# motor_driver_1.net
KiCad netlist of a schematic drawn in Altium Designer
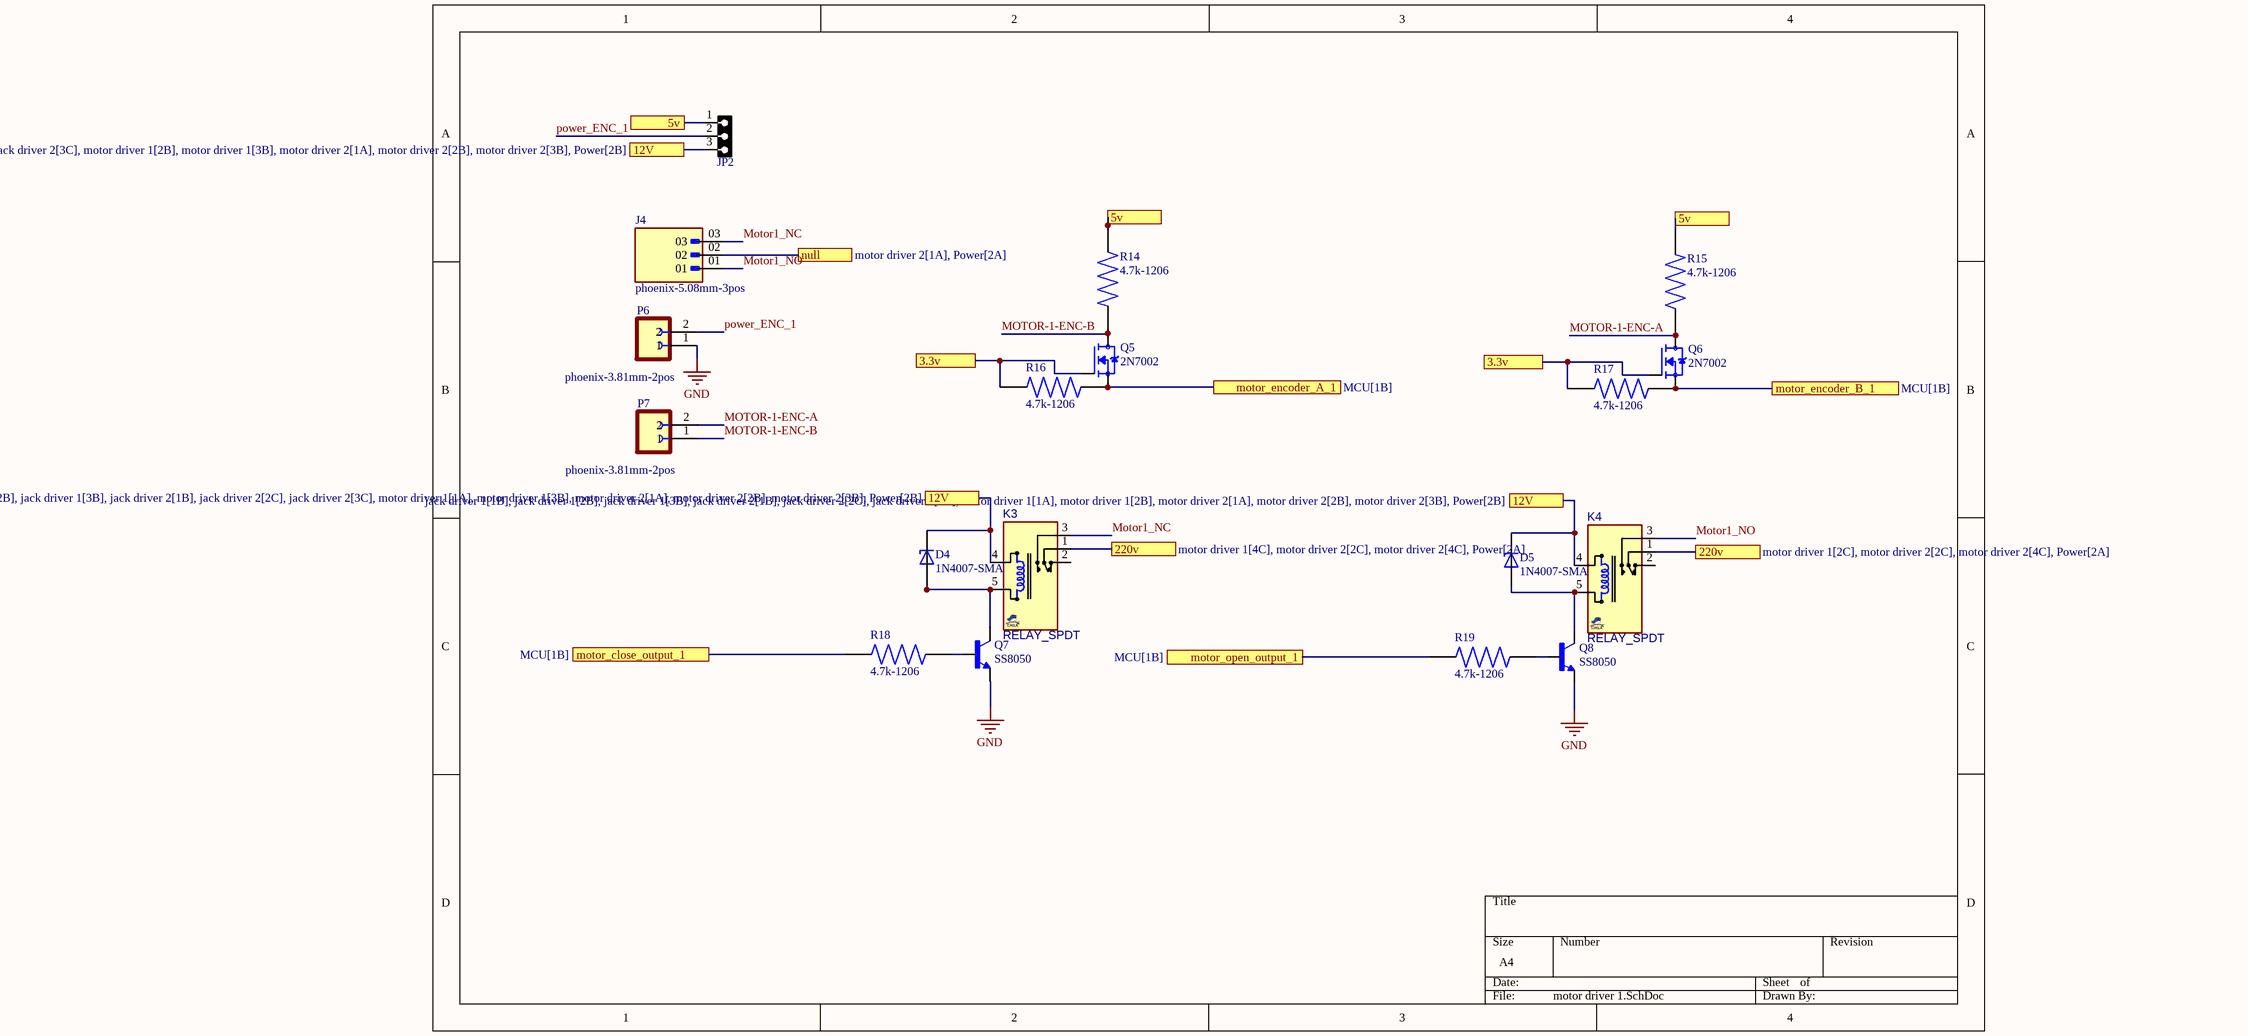
[diagram p0: motor driver 1.SchDoc]

(export (version "E")
  (design (tool "Eeschema 10.0.6"))
  (components
    (comp (ref "D4")
      (value "1N4007-SMA")
      (footprint "DIOM4325X250N")
      (description "400W, 30.4V, 5%, Unidirectional, TVS")
      (fields (field (name "MF") "Taiwan Semiconductor") (field (name "MP") "SMAJ26A"))
      (libsource (lib "diode-sma") (part "SMAJ26A"))
    )
    (comp (ref "D5")
      (value "1N4007-SMA")
      (footprint "DIOM4325X250N")
      (description "400W, 30.4V, 5%, Unidirectional, TVS")
      (fields (field (name "MF") "Taiwan Semiconductor") (field (name "MP") "SMAJ26A"))
      (libsource (lib "diode-sma") (part "SMAJ26A"))
    )
    (comp (ref "J4")
      (value "phoenix-5.08mm-3pos")
      (footprint "PHOENIX_1759020")
      (description "Pluggable Header 5.08mm 12AWG 320V 12A 3 Position COMBICON MSTB Series ¦ Phoenix Contact 1759020")
      (fields (field (name "MF") "Phoenix Contact") (field (name "MP") "1759020"))
      (libsource (lib "phoenix-3pos") (part "1759020"))
    )
    (comp (ref "JP2")
      (value "HDRF3")
      (footprint "HDRLP_F_1X3")
      (description "CONN, HEADER, Male, pitch: 2.54mm, 3POS")
      (libsource (lib "conn_2.54mm_lp") (part "HDRLP_F_1X3"))
    )
    (comp (ref "K3")
      (value "RELAY_SPDT")
      (footprint "REL_SPDT_5_1512")
      (description "Relay, SPDT, 5P, 15.4X12.1mm, 16V/30A")
      (fields (field (name "MANF") "OMRON") (field (name "MANF_P#") "G8QN-1C4 DC12"))
      (libsource (lib "relay") (part "RELAY_SPDT_5_1512_G8QN"))
    )
    (comp (ref "K4")
      (value "RELAY_SPDT")
      (footprint "REL_SPDT_5_1512")
      (description "Relay, SPDT, 5P, 15.4X12.1mm, 16V/30A")
      (fields (field (name "MANF") "OMRON") (field (name "MANF_P#") "G8QN-1C4 DC12"))
      (libsource (lib "relay") (part "RELAY_SPDT_5_1512_G8QN"))
    )
    (comp (ref "P6")
      (value "phoenix-3.81mm-2pos")
      (footprint "PHOENIX_1803578")
      (description "2 Position Terminal Block Plug, Female Sockets 0.150 (3.81mm) 180Â° Free Hanging (In-Line)")
      (fields (field (name "MF") "Phoenix Contact") (field (name "MP") "1803578"))
      (libsource (lib "terminal-phoenix-3.81mm-2pos") (part "1803578"))
    )
    (comp (ref "P7")
      (value "phoenix-3.81mm-2pos")
      (footprint "PHOENIX_1803578")
      (description "2 Position Terminal Block Plug, Female Sockets 0.150 (3.81mm) 180Â° Free Hanging (In-Line)")
      (fields (field (name "MF") "Phoenix Contact") (field (name "MP") "1803578"))
      (libsource (lib "terminal-phoenix-3.81mm-2pos") (part "1803578"))
    )
    (comp (ref "Q5")
      (value "2N7002")
      (footprint "SOT95P240X111-3N")
      (description "N-Channel 60V 280mA (Ta) 350mW (Ta) Surface Mount SOT-23-3 (TO-236)")
      (fields (field (name "MF") "{'manufacturer': u'onsemi'}"))
      (libsource (lib "2N7002-SOT23") (part "2N7002"))
    )
    (comp (ref "Q6")
      (value "2N7002")
      (footprint "SOT95P240X111-3N")
      (description "N-Channel 60V 280mA (Ta) 350mW (Ta) Surface Mount SOT-23-3 (TO-236)")
      (fields (field (name "MF") "{'manufacturer': u'onsemi'}"))
      (libsource (lib "2N7002-SOT23") (part "2N7002"))
    )
    (comp (ref "Q7")
      (value "SS8050")
      (footprint "TRANS_SS8050-G")
      (description "Bipolar (BJT) Transistor NPN 25 V 1.5 A 100MHz 300 mW Surface Mount SOT-23-3")
      (fields (field (name "DIGI-KEY_PART_NUMBER") "641-1790-2-ND") (field (name "MP") "SS8050G"))
      (libsource (lib "SS8050-G") (part "SS8050-G"))
    )
    (comp (ref "Q8")
      (value "SS8050")
      (footprint "TRANS_SS8050-G")
      (description "Bipolar (BJT) Transistor NPN 25 V 1.5 A 100MHz 300 mW Surface Mount SOT-23-3")
      (fields (field (name "DIGI-KEY_PART_NUMBER") "641-1790-2-ND") (field (name "MP") "SS8050G"))
      (libsource (lib "SS8050-G") (part "SS8050-G"))
    )
    (comp (ref "R14")
      (value "4.7k-1206")
      (footprint "RESC3015X65N")
      (description "Res Thin Film 1206 10K Ohm 0.1% 1/8W Â±25ppm/Â°C Molded SMD SMD Paper T/R")
      (fields (field (name "MF") "TE Connectivity") (field (name "MP") "CPF1206B10KE1"))
      (libsource (lib "resistor-1206") (part "CPF1206B10KE1"))
    )
    (comp (ref "R15")
      (value "4.7k-1206")
      (footprint "RESC3015X65N")
      (description "Res Thin Film 1206 10K Ohm 0.1% 1/8W Â±25ppm/Â°C Molded SMD SMD Paper T/R")
      (fields (field (name "MF") "TE Connectivity") (field (name "MP") "CPF1206B10KE1"))
      (libsource (lib "resistor-1206") (part "CPF1206B10KE1"))
    )
    (comp (ref "R16")
      (value "4.7k-1206")
      (footprint "RESC3015X65N")
      (description "Res Thin Film 1206 10K Ohm 0.1% 1/8W Â±25ppm/Â°C Molded SMD SMD Paper T/R")
      (fields (field (name "MF") "TE Connectivity") (field (name "MP") "CPF1206B10KE1"))
      (libsource (lib "resistor-1206") (part "CPF1206B10KE1"))
    )
    (comp (ref "R17")
      (value "4.7k-1206")
      (footprint "RESC3015X65N")
      (description "Res Thin Film 1206 10K Ohm 0.1% 1/8W Â±25ppm/Â°C Molded SMD SMD Paper T/R")
      (fields (field (name "MF") "TE Connectivity") (field (name "MP") "CPF1206B10KE1"))
      (libsource (lib "resistor-1206") (part "CPF1206B10KE1"))
    )
    (comp (ref "R18")
      (value "4.7k-1206")
      (footprint "RESC3015X65N")
      (description "Res Thin Film 1206 10K Ohm 0.1% 1/8W Â±25ppm/Â°C Molded SMD SMD Paper T/R")
      (fields (field (name "MF") "TE Connectivity") (field (name "MP") "CPF1206B10KE1"))
      (libsource (lib "resistor-1206") (part "CPF1206B10KE1"))
    )
    (comp (ref "R19")
      (value "4.7k-1206")
      (footprint "RESC3015X65N")
      (description "Res Thin Film 1206 10K Ohm 0.1% 1/8W Â±25ppm/Â°C Molded SMD SMD Paper T/R")
      (fields (field (name "MF") "TE Connectivity") (field (name "MP") "CPF1206B10KE1"))
      (libsource (lib "resistor-1206") (part "CPF1206B10KE1"))
    )
  )
  (nets
    (net (code "1") (name "/3.3v") (class "Default")
      (node (ref "Q5") (pin "1") (pinfunction "G_1") (pintype "passive"))
      (node (ref "Q6") (pin "1") (pinfunction "G_1") (pintype "passive"))
      (node (ref "R16") (pin "2") (pinfunction "2_2") (pintype "passive"))
      (node (ref "R17") (pin "2") (pinfunction "2_2") (pintype "passive"))
    )
    (net (code "2") (name "/5v") (class "Default")
      (node (ref "JP2") (pin "1") (pinfunction "1_1") (pintype "passive"))
      (node (ref "R14") (pin "2") (pinfunction "2_2") (pintype "passive"))
      (node (ref "R15") (pin "2") (pinfunction "2_2") (pintype "passive"))
    )
    (net (code "3") (name "/12V") (class "Default")
      (node (ref "D4") (pin "C") (pinfunction "C_C") (pintype "passive"))
      (node (ref "D5") (pin "C") (pinfunction "C_C") (pintype "passive"))
      (node (ref "JP2") (pin "3") (pinfunction "3_3") (pintype "passive"))
      (node (ref "K3") (pin "4") (pinfunction "T1_4") (pintype "passive"))
      (node (ref "K4") (pin "4") (pinfunction "T1_4") (pintype "passive"))
    )
    (net (code "4") (name "/220v") (class "Default")
      (node (ref "K3") (pin "1") (pinfunction "COM_1") (pintype "passive"))
      (node (ref "K4") (pin "1") (pinfunction "COM_1") (pintype "passive"))
    )
    (net (code "5") (name "/MOTOR-1-ENC-A") (class "Default")
      (node (ref "P7") (pin "2") (pinfunction "2_2") (pintype "passive"))
      (node (ref "Q6") (pin "3") (pinfunction "D_3") (pintype "passive"))
      (node (ref "R15") (pin "1") (pinfunction "1_1") (pintype "passive"))
    )
    (net (code "6") (name "/MOTOR-1-ENC-B") (class "Default")
      (node (ref "P7") (pin "1") (pinfunction "1_1") (pintype "passive"))
      (node (ref "Q5") (pin "3") (pinfunction "D_3") (pintype "passive"))
      (node (ref "R14") (pin "1") (pinfunction "1_1") (pintype "passive"))
    )
    (net (code "7") (name "/Motor1_NC") (class "Default")
      (node (ref "J4") (pin "03") (pinfunction "03_03") (pintype "passive"))
      (node (ref "K3") (pin "3") (pinfunction "NO_3") (pintype "passive"))
    )
    (net (code "8") (name "/Motor1_NO") (class "Default")
      (node (ref "J4") (pin "01") (pinfunction "01_01") (pintype "passive"))
      (node (ref "K4") (pin "3") (pinfunction "NO_3") (pintype "passive"))
    )
    (net (code "9") (name "/motor_close_output_1") (class "Default")
      (node (ref "R18") (pin "2") (pinfunction "2_2") (pintype "passive"))
    )
    (net (code "10") (name "/motor_encoder_A_1") (class "Default")
      (node (ref "Q5") (pin "2") (pinfunction "S_2") (pintype "passive"))
      (node (ref "R16") (pin "1") (pinfunction "1_1") (pintype "passive"))
    )
    (net (code "11") (name "/motor_encoder_B_1") (class "Default")
      (node (ref "Q6") (pin "2") (pinfunction "S_2") (pintype "passive"))
      (node (ref "R17") (pin "1") (pinfunction "1_1") (pintype "passive"))
    )
    (net (code "12") (name "/motor_open_output_1") (class "Default")
      (node (ref "R19") (pin "2") (pinfunction "2_2") (pintype "passive"))
    )
    (net (code "13") (name "/null") (class "Default")
      (node (ref "J4") (pin "02") (pinfunction "02_02") (pintype "passive"))
    )
    (net (code "14") (name "/power_ENC_1") (class "Default")
      (node (ref "JP2") (pin "2") (pinfunction "2_2") (pintype "passive"))
      (node (ref "P6") (pin "2") (pinfunction "2_2") (pintype "passive"))
    )
    (net (code "15") (name "GND") (class "Default")
      (node (ref "P6") (pin "1") (pinfunction "1_1") (pintype "passive"))
      (node (ref "Q7") (pin "2") (pinfunction "E_2") (pintype "passive"))
      (node (ref "Q8") (pin "2") (pinfunction "E_2") (pintype "passive"))
    )
    (net (code "16") (name "Net-(K3-T2)") (class "Default")
      (node (ref "D4") (pin "A") (pinfunction "A_A") (pintype "passive"))
      (node (ref "K3") (pin "5") (pinfunction "T2_5") (pintype "passive"))
      (node (ref "Q7") (pin "3") (pinfunction "C_3") (pintype "passive"))
    )
    (net (code "17") (name "Net-(K4-T2)") (class "Default")
      (node (ref "D5") (pin "A") (pinfunction "A_A") (pintype "passive"))
      (node (ref "K4") (pin "5") (pinfunction "T2_5") (pintype "passive"))
      (node (ref "Q8") (pin "3") (pinfunction "C_3") (pintype "passive"))
    )
    (net (code "18") (name "Net-(Q7-B)") (class "Default")
      (node (ref "Q7") (pin "1") (pinfunction "B_1") (pintype "passive"))
      (node (ref "R18") (pin "1") (pinfunction "1_1") (pintype "passive"))
    )
    (net (code "19") (name "Net-(Q8-B)") (class "Default")
      (node (ref "Q8") (pin "1") (pinfunction "B_1") (pintype "passive"))
      (node (ref "R19") (pin "1") (pinfunction "1_1") (pintype "passive"))
    )
    (net (code "20") (name "unconnected-(K3-NC-Pad2)") (class "Default")
      (node (ref "K3") (pin "2") (pinfunction "NC_2") (pintype "passive"))
    )
    (net (code "21") (name "unconnected-(K4-NC-Pad2)") (class "Default")
      (node (ref "K4") (pin "2") (pinfunction "NC_2") (pintype "passive"))
    )
  )
)
